# ADC.net
KiCad netlist of a schematic drawn in Altium Designer
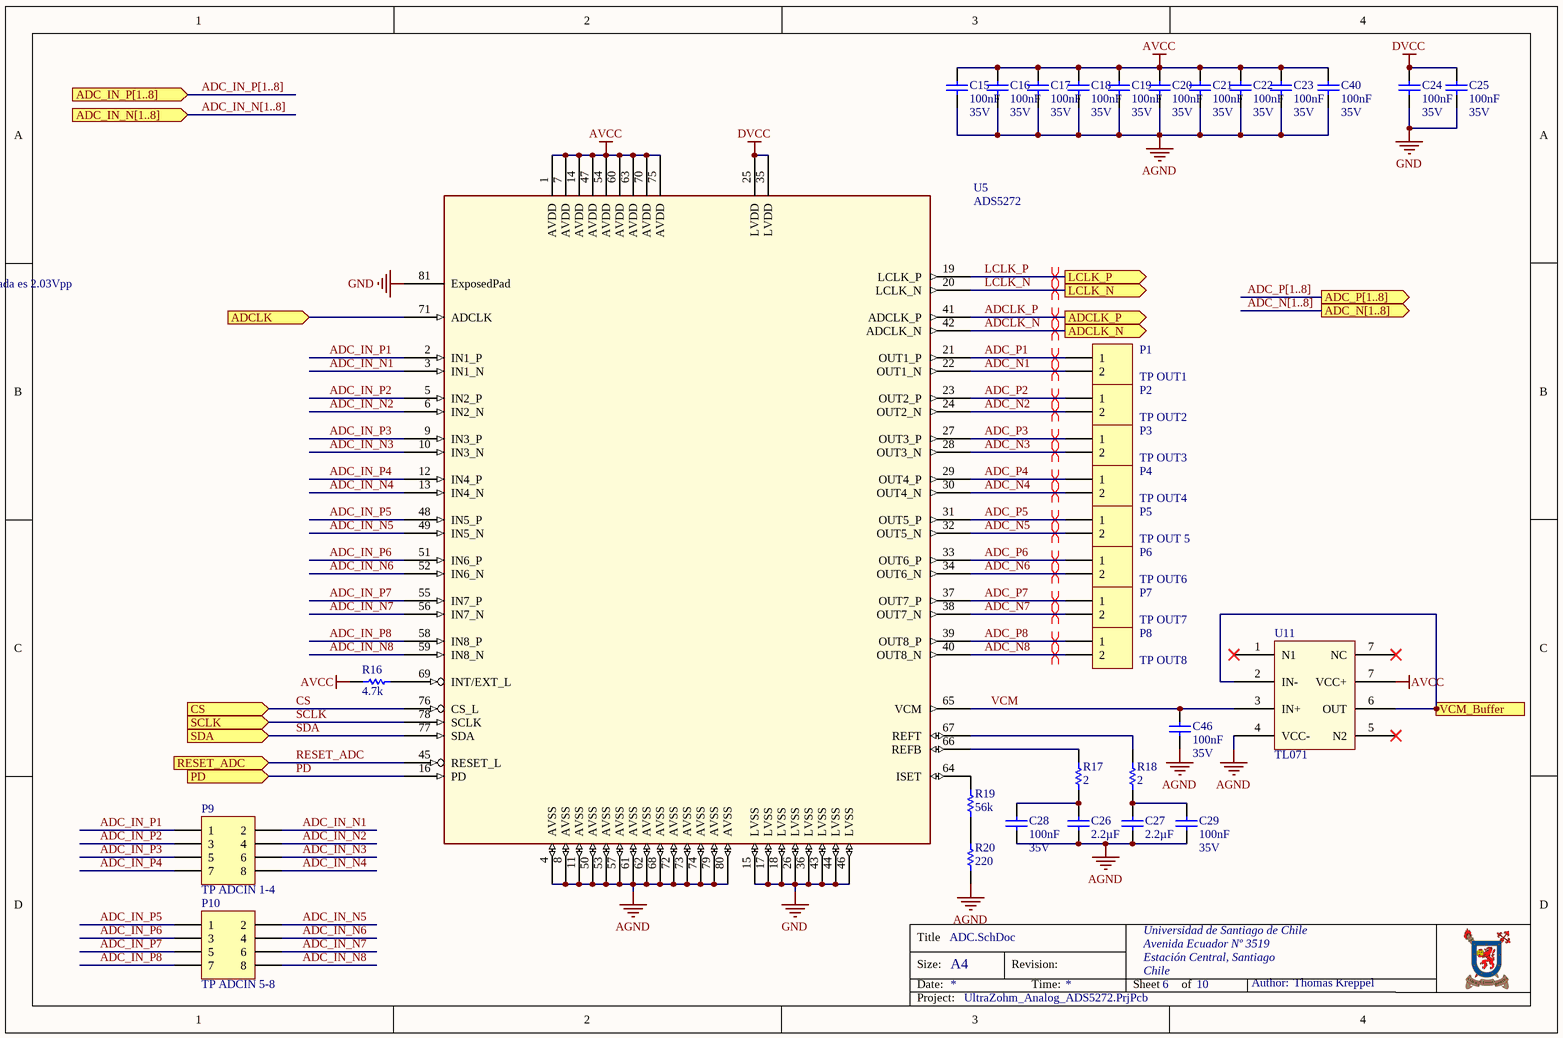
[diagram p0: ADC.SchDoc]

(export (version "E")
  (design (tool "Eeschema 10.0.6"))
  (components
    (comp (ref "C15")
      (value "100nF")
      (footprint "CAP_0603")
      (description "Capacitor")
      (fields
        (field (name "MPN") "C0603C104M5RACTU")
        (field (name "MF") "KEMET")
        (field (name "VOLTAGE") "35V")
        (field (name "PUBLISHER") "Altium Limited")
      )
      (libsource (lib "Componentes_SOC") (part "Cap_0603"))
    )
    (comp (ref "C16")
      (value "100nF")
      (footprint "CAP_0603")
      (description "Capacitor")
      (fields
        (field (name "MPN") "C0603C104M5RACTU")
        (field (name "MF") "KEMET")
        (field (name "VOLTAGE") "35V")
        (field (name "PUBLISHER") "Altium Limited")
      )
      (libsource (lib "Componentes_SOC") (part "Cap_0603"))
    )
    (comp (ref "C17")
      (value "100nF")
      (footprint "CAP_0603")
      (description "Capacitor")
      (fields
        (field (name "MPN") "C0603C104M5RACTU")
        (field (name "MF") "KEMET")
        (field (name "VOLTAGE") "35V")
        (field (name "PUBLISHER") "Altium Limited")
      )
      (libsource (lib "Componentes_SOC") (part "Cap_0603"))
    )
    (comp (ref "C18")
      (value "100nF")
      (footprint "CAP_0603")
      (description "Capacitor")
      (fields
        (field (name "MPN") "C0603C104M5RACTU")
        (field (name "MF") "KEMET")
        (field (name "VOLTAGE") "35V")
        (field (name "PUBLISHER") "Altium Limited")
      )
      (libsource (lib "Componentes_SOC") (part "Cap_0603"))
    )
    (comp (ref "C19")
      (value "100nF")
      (footprint "CAP_0603")
      (description "Capacitor")
      (fields
        (field (name "MPN") "C0603C104M5RACTU")
        (field (name "MF") "KEMET")
        (field (name "VOLTAGE") "35V")
        (field (name "PUBLISHER") "Altium Limited")
      )
      (libsource (lib "Componentes_SOC") (part "Cap_0603"))
    )
    (comp (ref "C20")
      (value "100nF")
      (footprint "CAP_0603")
      (description "Capacitor")
      (fields
        (field (name "MPN") "C0603C104M5RACTU")
        (field (name "MF") "KEMET")
        (field (name "VOLTAGE") "35V")
        (field (name "PUBLISHER") "Altium Limited")
      )
      (libsource (lib "Componentes_SOC") (part "Cap_0603"))
    )
    (comp (ref "C21")
      (value "100nF")
      (footprint "CAP_0603")
      (description "Capacitor")
      (fields
        (field (name "MPN") "C0603C104M5RACTU")
        (field (name "MF") "KEMET")
        (field (name "VOLTAGE") "35V")
        (field (name "PUBLISHER") "Altium Limited")
      )
      (libsource (lib "Componentes_SOC") (part "Cap_0603"))
    )
    (comp (ref "C22")
      (value "100nF")
      (footprint "CAP_0603")
      (description "Capacitor")
      (fields
        (field (name "MPN") "C0603C104M5RACTU")
        (field (name "MF") "KEMET")
        (field (name "VOLTAGE") "35V")
        (field (name "PUBLISHER") "Altium Limited")
      )
      (libsource (lib "Componentes_SOC") (part "Cap_0603"))
    )
    (comp (ref "C23")
      (value "100nF")
      (footprint "CAP_0603")
      (description "Capacitor")
      (fields
        (field (name "MPN") "C0603C104M5RACTU")
        (field (name "MF") "KEMET")
        (field (name "VOLTAGE") "35V")
        (field (name "PUBLISHER") "Altium Limited")
      )
      (libsource (lib "Componentes_SOC") (part "Cap_0603"))
    )
    (comp (ref "C24")
      (value "100nF")
      (footprint "CAP_0603")
      (description "Capacitor")
      (fields
        (field (name "MPN") "C0603C104M5RACTU")
        (field (name "MF") "KEMET")
        (field (name "VOLTAGE") "35V")
        (field (name "PUBLISHER") "Altium Limited")
      )
      (libsource (lib "Componentes_SOC") (part "Cap_0603"))
    )
    (comp (ref "C25")
      (value "100nF")
      (footprint "CAP_0603")
      (description "Capacitor")
      (fields
        (field (name "MPN") "C0603C104M5RACTU")
        (field (name "MF") "KEMET")
        (field (name "VOLTAGE") "35V")
        (field (name "PUBLISHER") "Altium Limited")
      )
      (libsource (lib "Componentes_SOC") (part "Cap_0603"))
    )
    (comp (ref "C26")
      (value "2.2µF")
      (footprint "CAP_0603")
      (description "Capacitor")
      (fields
        (field (name "MPN") "C0603C225K8RACTU")
        (field (name "MF") "KEMET")
        (field (name "PUBLISHER") "Altium Limited")
      )
      (libsource (lib "Componentes_SOC") (part "Cap_0603"))
    )
    (comp (ref "C27")
      (value "2.2µF")
      (footprint "CAP_0603")
      (description "Capacitor")
      (fields
        (field (name "MPN") "C0603C225K8RACTU")
        (field (name "MF") "KEMET")
        (field (name "PUBLISHER") "Altium Limited")
      )
      (libsource (lib "Componentes_SOC") (part "Cap_0603"))
    )
    (comp (ref "C28")
      (value "100nF")
      (footprint "CAP_0603")
      (description "Capacitor")
      (fields
        (field (name "MPN") "C0603C104M5RACTU")
        (field (name "MF") "KEMET")
        (field (name "VOLTAGE") "35V")
        (field (name "PUBLISHER") "Altium Limited")
      )
      (libsource (lib "Componentes_SOC") (part "Cap_0603"))
    )
    (comp (ref "C29")
      (value "100nF")
      (footprint "CAP_0603")
      (description "Capacitor")
      (fields
        (field (name "MPN") "C0603C104M5RACTU")
        (field (name "MF") "KEMET")
        (field (name "VOLTAGE") "35V")
        (field (name "PUBLISHER") "Altium Limited")
      )
      (libsource (lib "Componentes_SOC") (part "Cap_0603"))
    )
    (comp (ref "C40")
      (value "100nF")
      (footprint "CAP_0603")
      (description "Capacitor")
      (fields
        (field (name "MPN") "C0603C104M5RACTU")
        (field (name "MF") "KEMET")
        (field (name "VOLTAGE") "35V")
        (field (name "PUBLISHER") "Altium Limited")
      )
      (libsource (lib "Componentes_SOC") (part "Cap_0603"))
    )
    (comp (ref "C46")
      (value "100nF")
      (footprint "CAP_0603")
      (description "Capacitor")
      (fields
        (field (name "MPN") "C0603C104M5RACTU")
        (field (name "MF") "KEMET")
        (field (name "VOLTAGE") "35V")
        (field (name "PUBLISHER") "Altium Limited")
      )
      (libsource (lib "Componentes_SOC") (part "Cap_0603"))
    )
    (comp (ref "P1")
      (value "TP OUT1")
      (footprint "HDR1X2")
      (description "Header, 2-Pin")
      (fields (field (name "PUBLISHER") "Altium Limited"))
      (libsource (lib "Miscellaneous Connectors") (part "Header 2"))
    )
    (comp (ref "P2")
      (value "TP OUT2")
      (footprint "HDR1X2")
      (description "Header, 2-Pin")
      (fields (field (name "PUBLISHER") "Altium Limited"))
      (libsource (lib "Miscellaneous Connectors") (part "Header 2"))
    )
    (comp (ref "P3")
      (value "TP OUT3")
      (footprint "HDR1X2")
      (description "Header, 2-Pin")
      (fields (field (name "PUBLISHER") "Altium Limited"))
      (libsource (lib "Miscellaneous Connectors") (part "Header 2"))
    )
    (comp (ref "P4")
      (value "TP OUT4")
      (footprint "HDR1X2")
      (description "Header, 2-Pin")
      (fields (field (name "PUBLISHER") "Altium Limited"))
      (libsource (lib "Miscellaneous Connectors") (part "Header 2"))
    )
    (comp (ref "P5")
      (value "TP OUT 5")
      (footprint "HDR1X2")
      (description "Header, 2-Pin")
      (fields (field (name "PUBLISHER") "Altium Limited"))
      (libsource (lib "Miscellaneous Connectors") (part "Header 2"))
    )
    (comp (ref "P6")
      (value "TP OUT6")
      (footprint "HDR1X2")
      (description "Header, 2-Pin")
      (fields (field (name "PUBLISHER") "Altium Limited"))
      (libsource (lib "Miscellaneous Connectors") (part "Header 2"))
    )
    (comp (ref "P7")
      (value "TP OUT7")
      (footprint "HDR1X2")
      (description "Header, 2-Pin")
      (fields (field (name "PUBLISHER") "Altium Limited"))
      (libsource (lib "Miscellaneous Connectors") (part "Header 2"))
    )
    (comp (ref "P8")
      (value "TP OUT8")
      (footprint "HDR1X2")
      (description "Header, 2-Pin")
      (fields (field (name "PUBLISHER") "Altium Limited"))
      (libsource (lib "Miscellaneous Connectors") (part "Header 2"))
    )
    (comp (ref "P9")
      (value "TP ADCIN 1-4")
      (footprint "HDR2X4")
      (description "Header, 4-Pin, Dual row")
      (fields (field (name "PUBLISHER") "Altium Limited"))
      (libsource (lib "Miscellaneous Connectors") (part "Header 4X2"))
    )
    (comp (ref "P10")
      (value "TP ADCIN 5-8")
      (footprint "HDR2X4")
      (description "Header, 4-Pin, Dual row")
      (fields (field (name "PUBLISHER") "Altium Limited"))
      (libsource (lib "Miscellaneous Connectors") (part "Header 4X2"))
    )
    (comp (ref "R16")
      (value "4.7k")
      (footprint "RES_0603")
      (fields (field (name "TOLERANCE") "1%") (field (name "PUBLISHER") "Altium Limited"))
      (libsource (lib "Componentes_SOC") (part "Res0603"))
    )
    (comp (ref "R17")
      (value "2")
      (footprint "RES_0603")
      (fields (field (name "TOLERANCE") "1%") (field (name "PUBLISHER") "Altium Limited"))
      (libsource (lib "Componentes_SOC") (part "Res0603"))
    )
    (comp (ref "R18")
      (value "2")
      (footprint "RES_0603")
      (fields (field (name "TOLERANCE") "1%") (field (name "PUBLISHER") "Altium Limited"))
      (libsource (lib "Componentes_SOC") (part "Res0603"))
    )
    (comp (ref "R19")
      (value "56k")
      (footprint "RES_0603")
      (fields (field (name "TOLERANCE") "1%") (field (name "PUBLISHER") "Altium Limited"))
      (libsource (lib "Componentes_SOC") (part "Res0603"))
    )
    (comp (ref "R20")
      (value "220")
      (footprint "RES_0603")
      (fields (field (name "TOLERANCE") "1%") (field (name "PUBLISHER") "Altium Limited"))
      (libsource (lib "Componentes_SOC") (part "Res0603"))
    )
    (comp (ref "U5")
      (value "ADS5272")
      (footprint "TSQFP50P1400X1400_HS-80M")
      (libsource (lib "Componentes_SOC") (part "ADS5272"))
    )
    (comp (ref "U11")
      (value "TL071")
      (footprint "SOIC8_N")
      (description "IC OPAMP JFET 3MHZ 8SOIC")
      (libsource (lib "Componentes_SOC") (part "TL071"))
    )
  )
  (nets
    (net (code "1") (name "/ADCLK") (class "Default")
      (node (ref "U5") (pin "71") (pinfunction "ADCLK_71") (pintype "input"))
    )
    (net (code "2") (name "/ADCLK_N") (class "Default")
      (node (ref "U5") (pin "42") (pinfunction "ADCLK_N_42") (pintype "output"))
    )
    (net (code "3") (name "/ADCLK_P") (class "Default")
      (node (ref "U5") (pin "41") (pinfunction "ADCLK_P_41") (pintype "output"))
    )
    (net (code "4") (name "/ADC_IN_N1") (class "Default")
      (node (ref "P9") (pin "2") (pinfunction "2_2") (pintype "passive"))
      (node (ref "U5") (pin "3") (pinfunction "IN1_N_3") (pintype "input"))
    )
    (net (code "5") (name "/ADC_IN_N2") (class "Default")
      (node (ref "P9") (pin "4") (pinfunction "4_4") (pintype "passive"))
      (node (ref "U5") (pin "6") (pinfunction "IN2_N_6") (pintype "input"))
    )
    (net (code "6") (name "/ADC_IN_N3") (class "Default")
      (node (ref "P9") (pin "6") (pinfunction "6_6") (pintype "passive"))
      (node (ref "U5") (pin "10") (pinfunction "IN3_N_10") (pintype "input"))
    )
    (net (code "7") (name "/ADC_IN_N4") (class "Default")
      (node (ref "P9") (pin "8") (pinfunction "8_8") (pintype "passive"))
      (node (ref "U5") (pin "13") (pinfunction "IN4_N_13") (pintype "input"))
    )
    (net (code "8") (name "/ADC_IN_N5") (class "Default")
      (node (ref "P10") (pin "2") (pinfunction "2_2") (pintype "passive"))
      (node (ref "U5") (pin "49") (pinfunction "IN5_N_49") (pintype "input"))
    )
    (net (code "9") (name "/ADC_IN_N6") (class "Default")
      (node (ref "P10") (pin "4") (pinfunction "4_4") (pintype "passive"))
      (node (ref "U5") (pin "52") (pinfunction "IN6_N_52") (pintype "input"))
    )
    (net (code "10") (name "/ADC_IN_N7") (class "Default")
      (node (ref "P10") (pin "6") (pinfunction "6_6") (pintype "passive"))
      (node (ref "U5") (pin "56") (pinfunction "IN7_N_56") (pintype "input"))
    )
    (net (code "11") (name "/ADC_IN_N8") (class "Default")
      (node (ref "P10") (pin "8") (pinfunction "8_8") (pintype "passive"))
      (node (ref "U5") (pin "59") (pinfunction "IN8_N_59") (pintype "input"))
    )
    (net (code "13") (name "/ADC_IN_P1") (class "Default")
      (node (ref "P9") (pin "1") (pinfunction "1_1") (pintype "passive"))
      (node (ref "U5") (pin "2") (pinfunction "IN1_P_2") (pintype "input"))
    )
    (net (code "14") (name "/ADC_IN_P2") (class "Default")
      (node (ref "P9") (pin "3") (pinfunction "3_3") (pintype "passive"))
      (node (ref "U5") (pin "5") (pinfunction "IN2_P_5") (pintype "input"))
    )
    (net (code "15") (name "/ADC_IN_P3") (class "Default")
      (node (ref "P9") (pin "5") (pinfunction "5_5") (pintype "passive"))
      (node (ref "U5") (pin "9") (pinfunction "IN3_P_9") (pintype "input"))
    )
    (net (code "16") (name "/ADC_IN_P4") (class "Default")
      (node (ref "P9") (pin "7") (pinfunction "7_7") (pintype "passive"))
      (node (ref "U5") (pin "12") (pinfunction "IN4_P_12") (pintype "input"))
    )
    (net (code "17") (name "/ADC_IN_P5") (class "Default")
      (node (ref "P10") (pin "1") (pinfunction "1_1") (pintype "passive"))
      (node (ref "U5") (pin "48") (pinfunction "IN5_P_48") (pintype "input"))
    )
    (net (code "18") (name "/ADC_IN_P6") (class "Default")
      (node (ref "P10") (pin "3") (pinfunction "3_3") (pintype "passive"))
      (node (ref "U5") (pin "51") (pinfunction "IN6_P_51") (pintype "input"))
    )
    (net (code "19") (name "/ADC_IN_P7") (class "Default")
      (node (ref "P10") (pin "5") (pinfunction "5_5") (pintype "passive"))
      (node (ref "U5") (pin "55") (pinfunction "IN7_P_55") (pintype "input"))
    )
    (net (code "20") (name "/ADC_IN_P8") (class "Default")
      (node (ref "P10") (pin "7") (pinfunction "7_7") (pintype "passive"))
      (node (ref "U5") (pin "58") (pinfunction "IN8_P_58") (pintype "input"))
    )
    (net (code "22") (name "/ADC_N1") (class "Default")
      (node (ref "P1") (pin "2") (pinfunction "2_2") (pintype "passive"))
      (node (ref "U5") (pin "22") (pinfunction "OUT1_N_22") (pintype "output"))
    )
    (net (code "23") (name "/ADC_N2") (class "Default")
      (node (ref "P2") (pin "2") (pinfunction "2_2") (pintype "passive"))
      (node (ref "U5") (pin "24") (pinfunction "OUT2_N_24") (pintype "output"))
    )
    (net (code "24") (name "/ADC_N3") (class "Default")
      (node (ref "P3") (pin "2") (pinfunction "2_2") (pintype "passive"))
      (node (ref "U5") (pin "28") (pinfunction "OUT3_N_28") (pintype "output"))
    )
    (net (code "25") (name "/ADC_N4") (class "Default")
      (node (ref "P4") (pin "2") (pinfunction "2_2") (pintype "passive"))
      (node (ref "U5") (pin "30") (pinfunction "OUT4_N_30") (pintype "output"))
    )
    (net (code "26") (name "/ADC_N5") (class "Default")
      (node (ref "P5") (pin "2") (pinfunction "2_2") (pintype "passive"))
      (node (ref "U5") (pin "32") (pinfunction "OUT5_N_32") (pintype "output"))
    )
    (net (code "27") (name "/ADC_N6") (class "Default")
      (node (ref "P6") (pin "2") (pinfunction "2_2") (pintype "passive"))
      (node (ref "U5") (pin "34") (pinfunction "OUT6_N_34") (pintype "output"))
    )
    (net (code "28") (name "/ADC_N7") (class "Default")
      (node (ref "P7") (pin "2") (pinfunction "2_2") (pintype "passive"))
      (node (ref "U5") (pin "38") (pinfunction "OUT7_N_38") (pintype "output"))
    )
    (net (code "29") (name "/ADC_N8") (class "Default")
      (node (ref "P8") (pin "2") (pinfunction "2_2") (pintype "passive"))
      (node (ref "U5") (pin "40") (pinfunction "OUT8_N_40") (pintype "output"))
    )
    (net (code "31") (name "/ADC_P1") (class "Default")
      (node (ref "P1") (pin "1") (pinfunction "1_1") (pintype "passive"))
      (node (ref "U5") (pin "21") (pinfunction "OUT1_P_21") (pintype "output"))
    )
    (net (code "32") (name "/ADC_P2") (class "Default")
      (node (ref "P2") (pin "1") (pinfunction "1_1") (pintype "passive"))
      (node (ref "U5") (pin "23") (pinfunction "OUT2_P_23") (pintype "output"))
    )
    (net (code "33") (name "/ADC_P3") (class "Default")
      (node (ref "P3") (pin "1") (pinfunction "1_1") (pintype "passive"))
      (node (ref "U5") (pin "27") (pinfunction "OUT3_P_27") (pintype "output"))
    )
    (net (code "34") (name "/ADC_P4") (class "Default")
      (node (ref "P4") (pin "1") (pinfunction "1_1") (pintype "passive"))
      (node (ref "U5") (pin "29") (pinfunction "OUT4_P_29") (pintype "output"))
    )
    (net (code "35") (name "/ADC_P5") (class "Default")
      (node (ref "P5") (pin "1") (pinfunction "1_1") (pintype "passive"))
      (node (ref "U5") (pin "31") (pinfunction "OUT5_P_31") (pintype "output"))
    )
    (net (code "36") (name "/ADC_P6") (class "Default")
      (node (ref "P6") (pin "1") (pinfunction "1_1") (pintype "passive"))
      (node (ref "U5") (pin "33") (pinfunction "OUT6_P_33") (pintype "output"))
    )
    (net (code "37") (name "/ADC_P7") (class "Default")
      (node (ref "P7") (pin "1") (pinfunction "1_1") (pintype "passive"))
      (node (ref "U5") (pin "37") (pinfunction "OUT7_P_37") (pintype "output"))
    )
    (net (code "38") (name "/ADC_P8") (class "Default")
      (node (ref "P8") (pin "1") (pinfunction "1_1") (pintype "passive"))
      (node (ref "U5") (pin "39") (pinfunction "OUT8_P_39") (pintype "output"))
    )
    (net (code "40") (name "/CS") (class "Default")
      (node (ref "U5") (pin "76") (pinfunction "CS_L_76") (pintype "input"))
    )
    (net (code "41") (name "/LCLK_N") (class "Default")
      (node (ref "U5") (pin "20") (pinfunction "LCLK_N_20") (pintype "output"))
    )
    (net (code "42") (name "/LCLK_P") (class "Default")
      (node (ref "U5") (pin "19") (pinfunction "LCLK_P_19") (pintype "output"))
    )
    (net (code "43") (name "/PD") (class "Default")
      (node (ref "U5") (pin "16") (pinfunction "PD_16") (pintype "input"))
    )
    (net (code "44") (name "/RESET_ADC") (class "Default")
      (node (ref "U5") (pin "45") (pinfunction "RESET_L_45") (pintype "input"))
    )
    (net (code "45") (name "/SCLK") (class "Default")
      (node (ref "U5") (pin "78") (pinfunction "SCLK_78") (pintype "input"))
    )
    (net (code "46") (name "/SDA") (class "Default")
      (node (ref "U5") (pin "77") (pinfunction "SDA_77") (pintype "input"))
    )
    (net (code "47") (name "/VCM") (class "Default")
      (node (ref "C46") (pin "1") (pinfunction "1_1") (pintype "passive"))
      (node (ref "U11") (pin "3") (pinfunction "IN+_3") (pintype "passive"))
      (node (ref "U5") (pin "65") (pinfunction "VCM_65") (pintype "output"))
    )
    (net (code "48") (name "/VCM_Buffer") (class "Default")
      (node (ref "U11") (pin "2") (pinfunction "IN-_2") (pintype "passive"))
      (node (ref "U11") (pin "6") (pinfunction "OUT_6") (pintype "passive"))
    )
    (net (code "49") (name "AGND") (class "Default")
      (node (ref "C15") (pin "2") (pinfunction "2_2") (pintype "passive"))
      (node (ref "C16") (pin "2") (pinfunction "2_2") (pintype "passive"))
      (node (ref "C17") (pin "2") (pinfunction "2_2") (pintype "passive"))
      (node (ref "C18") (pin "2") (pinfunction "2_2") (pintype "passive"))
      (node (ref "C19") (pin "2") (pinfunction "2_2") (pintype "passive"))
      (node (ref "C20") (pin "2") (pinfunction "2_2") (pintype "passive"))
      (node (ref "C21") (pin "2") (pinfunction "2_2") (pintype "passive"))
      (node (ref "C22") (pin "2") (pinfunction "2_2") (pintype "passive"))
      (node (ref "C23") (pin "2") (pinfunction "2_2") (pintype "passive"))
      (node (ref "C26") (pin "2") (pinfunction "2_2") (pintype "passive"))
      (node (ref "C27") (pin "2") (pinfunction "2_2") (pintype "passive"))
      (node (ref "C28") (pin "2") (pinfunction "2_2") (pintype "passive"))
      (node (ref "C29") (pin "2") (pinfunction "2_2") (pintype "passive"))
      (node (ref "C40") (pin "2") (pinfunction "2_2") (pintype "passive"))
      (node (ref "C46") (pin "2") (pinfunction "2_2") (pintype "passive"))
      (node (ref "R20") (pin "1") (pinfunction "1_1") (pintype "passive"))
      (node (ref "U11") (pin "4") (pinfunction "VCC-_4") (pintype "passive"))
      (node (ref "U5") (pin "11") (pinfunction "AVSS_11") (pintype "bidirectional"))
      (node (ref "U5") (pin "4") (pinfunction "AVSS_4") (pintype "bidirectional"))
      (node (ref "U5") (pin "50") (pinfunction "AVSS_50") (pintype "bidirectional"))
      (node (ref "U5") (pin "53") (pinfunction "AVSS_53") (pintype "bidirectional"))
      (node (ref "U5") (pin "57") (pinfunction "AVSS_57") (pintype "bidirectional"))
      (node (ref "U5") (pin "61") (pinfunction "AVSS_61") (pintype "bidirectional"))
      (node (ref "U5") (pin "62") (pinfunction "AVSS_62") (pintype "bidirectional"))
      (node (ref "U5") (pin "68") (pinfunction "AVSS_68") (pintype "bidirectional"))
      (node (ref "U5") (pin "72") (pinfunction "AVSS_72") (pintype "bidirectional"))
      (node (ref "U5") (pin "73") (pinfunction "AVSS_73") (pintype "bidirectional"))
      (node (ref "U5") (pin "74") (pinfunction "AVSS_74") (pintype "bidirectional"))
      (node (ref "U5") (pin "79") (pinfunction "AVSS_79") (pintype "bidirectional"))
      (node (ref "U5") (pin "8") (pinfunction "AVSS_8") (pintype "bidirectional"))
      (node (ref "U5") (pin "80") (pinfunction "AVSS_80") (pintype "bidirectional"))
    )
    (net (code "50") (name "AVCC") (class "Default")
      (node (ref "C15") (pin "1") (pinfunction "1_1") (pintype "passive"))
      (node (ref "C16") (pin "1") (pinfunction "1_1") (pintype "passive"))
      (node (ref "C17") (pin "1") (pinfunction "1_1") (pintype "passive"))
      (node (ref "C18") (pin "1") (pinfunction "1_1") (pintype "passive"))
      (node (ref "C19") (pin "1") (pinfunction "1_1") (pintype "passive"))
      (node (ref "C20") (pin "1") (pinfunction "1_1") (pintype "passive"))
      (node (ref "C21") (pin "1") (pinfunction "1_1") (pintype "passive"))
      (node (ref "C22") (pin "1") (pinfunction "1_1") (pintype "passive"))
      (node (ref "C23") (pin "1") (pinfunction "1_1") (pintype "passive"))
      (node (ref "C40") (pin "1") (pinfunction "1_1") (pintype "passive"))
      (node (ref "R16") (pin "2") (pinfunction "2_2") (pintype "passive"))
      (node (ref "U11") (pin "7") (pinfunction "VCC+_7") (pintype "passive"))
      (node (ref "U5") (pin "1") (pinfunction "AVDD_1") (pintype "power_in"))
      (node (ref "U5") (pin "14") (pinfunction "AVDD_14") (pintype "power_in"))
      (node (ref "U5") (pin "47") (pinfunction "AVDD_47") (pintype "power_in"))
      (node (ref "U5") (pin "54") (pinfunction "AVDD_54") (pintype "power_in"))
      (node (ref "U5") (pin "60") (pinfunction "AVDD_60") (pintype "power_in"))
      (node (ref "U5") (pin "63") (pinfunction "AVDD_63") (pintype "power_in"))
      (node (ref "U5") (pin "7") (pinfunction "AVDD_7") (pintype "power_in"))
      (node (ref "U5") (pin "70") (pinfunction "AVDD_70") (pintype "power_in"))
      (node (ref "U5") (pin "75") (pinfunction "AVDD_75") (pintype "power_in"))
    )
    (net (code "51") (name "DVCC") (class "Default")
      (node (ref "C24") (pin "1") (pinfunction "1_1") (pintype "passive"))
      (node (ref "C25") (pin "1") (pinfunction "1_1") (pintype "passive"))
      (node (ref "U5") (pin "25") (pinfunction "LVDD_25") (pintype "power_in"))
      (node (ref "U5") (pin "35") (pinfunction "LVDD_35") (pintype "power_in"))
    )
    (net (code "52") (name "GND") (class "Default")
      (node (ref "C24") (pin "2") (pinfunction "2_2") (pintype "passive"))
      (node (ref "C25") (pin "2") (pinfunction "2_2") (pintype "passive"))
      (node (ref "U5") (pin "15") (pinfunction "LVSS_15") (pintype "bidirectional"))
      (node (ref "U5") (pin "17") (pinfunction "LVSS_17") (pintype "bidirectional"))
      (node (ref "U5") (pin "18") (pinfunction "LVSS_18") (pintype "bidirectional"))
      (node (ref "U5") (pin "26") (pinfunction "LVSS_26") (pintype "bidirectional"))
      (node (ref "U5") (pin "36") (pinfunction "LVSS_36") (pintype "bidirectional"))
      (node (ref "U5") (pin "43") (pinfunction "LVSS_43") (pintype "bidirectional"))
      (node (ref "U5") (pin "44") (pinfunction "LVSS_44") (pintype "bidirectional"))
      (node (ref "U5") (pin "46") (pinfunction "LVSS_46") (pintype "bidirectional"))
      (node (ref "U5") (pin "81") (pinfunction "ExposedPad_81") (pintype "passive"))
    )
    (net (code "53") (name "Net-(C26-Pad1)") (class "Default")
      (node (ref "C26") (pin "1") (pinfunction "1_1") (pintype "passive"))
      (node (ref "C28") (pin "1") (pinfunction "1_1") (pintype "passive"))
      (node (ref "R17") (pin "1") (pinfunction "1_1") (pintype "passive"))
    )
    (net (code "54") (name "Net-(C27-Pad1)") (class "Default")
      (node (ref "C27") (pin "1") (pinfunction "1_1") (pintype "passive"))
      (node (ref "C29") (pin "1") (pinfunction "1_1") (pintype "passive"))
      (node (ref "R18") (pin "1") (pinfunction "1_1") (pintype "passive"))
    )
    (net (code "55") (name "Net-(R19-Pad1)") (class "Default")
      (node (ref "R19") (pin "1") (pinfunction "1_1") (pintype "passive"))
      (node (ref "R20") (pin "2") (pinfunction "2_2") (pintype "passive"))
    )
    (net (code "56") (name "Net-(U5-INT{slash}EXT_L)") (class "Default")
      (node (ref "R16") (pin "1") (pinfunction "1_1") (pintype "passive"))
      (node (ref "U5") (pin "69") (pinfunction "INT/EXT_L_69") (pintype "input"))
    )
    (net (code "57") (name "Net-(U5-ISET)") (class "Default")
      (node (ref "R19") (pin "2") (pinfunction "2_2") (pintype "passive"))
      (node (ref "U5") (pin "64") (pinfunction "ISET_64") (pintype "bidirectional"))
    )
    (net (code "58") (name "Net-(U5-REFB)") (class "Default")
      (node (ref "R17") (pin "2") (pinfunction "2_2") (pintype "passive"))
      (node (ref "U5") (pin "66") (pinfunction "REFB_66") (pintype "bidirectional"))
    )
    (net (code "59") (name "Net-(U5-REFT)") (class "Default")
      (node (ref "R18") (pin "2") (pinfunction "2_2") (pintype "passive"))
      (node (ref "U5") (pin "67") (pinfunction "REFT_67") (pintype "bidirectional"))
    )
    (net (code "60") (name "unconnected-(U11-N1-Pad1)") (class "Default")
      (node (ref "U11") (pin "1") (pinfunction "N1_1") (pintype "passive+no_connect"))
    )
    (net (code "61") (name "unconnected-(U11-N2-Pad5)") (class "Default")
      (node (ref "U11") (pin "5") (pinfunction "N2_5") (pintype "passive+no_connect"))
    )
    (net (code "62") (name "unconnected-(U11-NC-Pad7)") (class "Default")
      (node (ref "U11") (pin "7") (pinfunction "NC_7") (pintype "passive+no_connect"))
    )
  )
)
